# Connections.net
KiCad netlist of a schematic drawn in Altium Designer
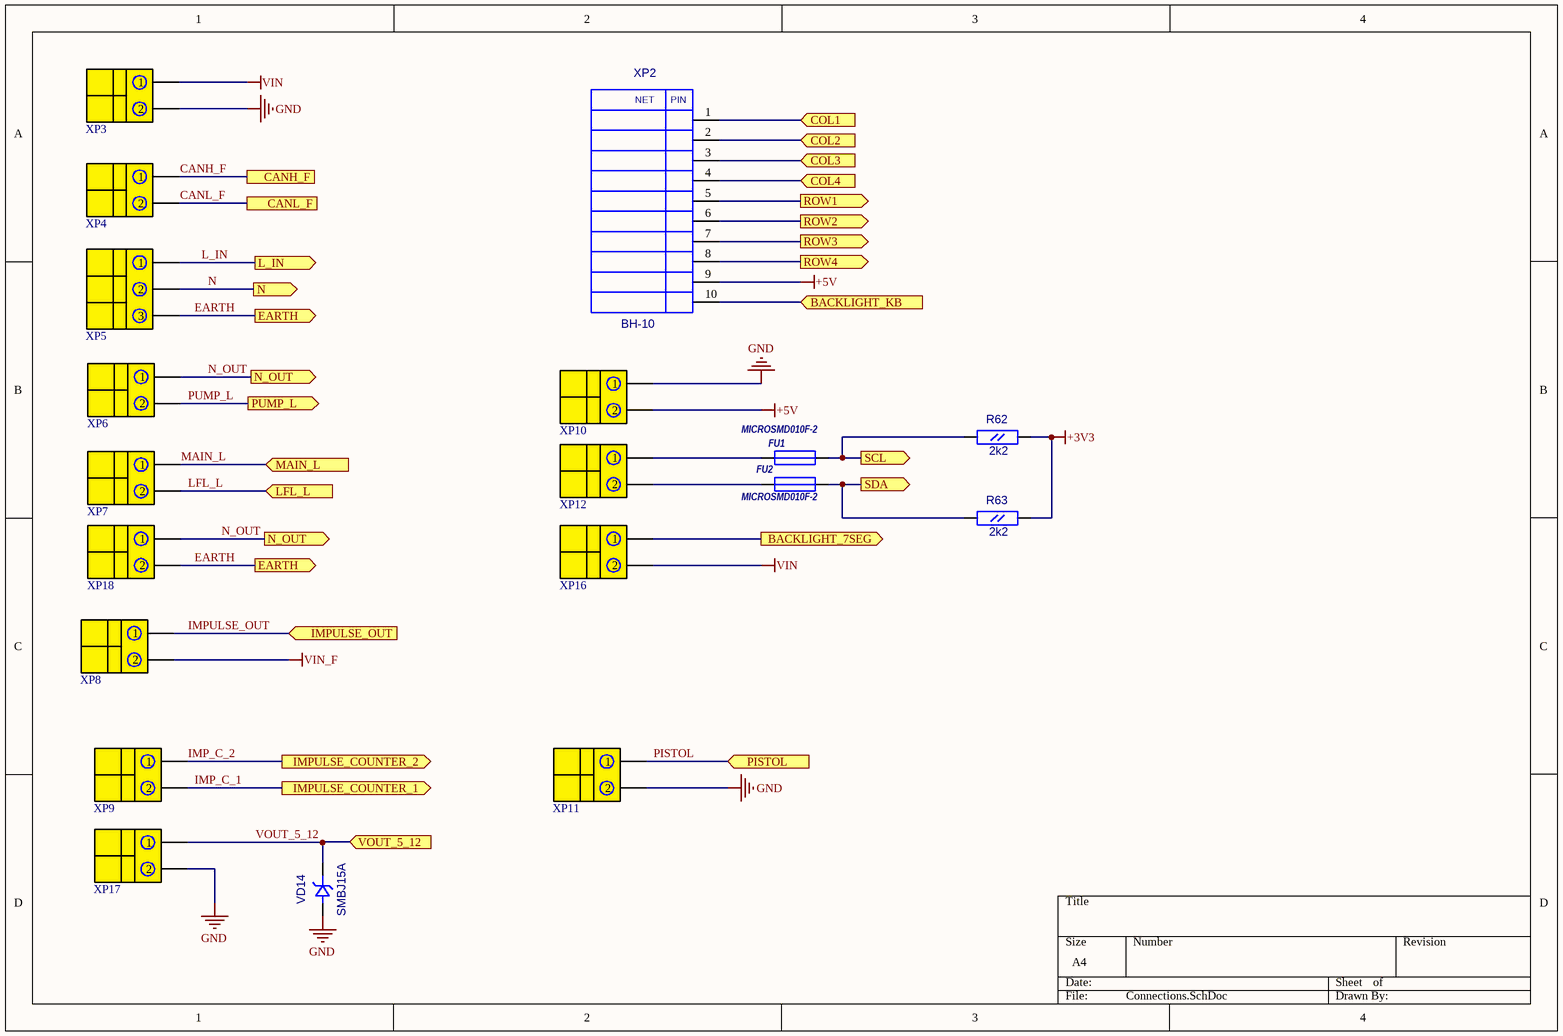
[diagram p0: Connections.SchDoc]

(export (version "E")
  (design (tool "Eeschema 10.0.6"))
  (components
    (comp (ref "FU1")
      (value "MICROSMD010F-2")
      (footprint "RC1210")
      (description "MICROSMD")
      (libsource (lib "gprs_modem_2") (part "MICROSMD"))
    )
    (comp (ref "FU2")
      (value "MICROSMD010F-2")
      (footprint "RC1210")
      (description "MICROSMD")
      (libsource (lib "gprs_modem_2") (part "MICROSMD"))
    )
    (comp (ref "R62")
      (value "2k2")
      (footprint "RC0603")
      (description "RC0603")
      (libsource (lib "gprs_modem_2") (part "RC0603"))
    )
    (comp (ref "R63")
      (value "2k2")
      (footprint "RC0603")
      (description "RC0603")
      (libsource (lib "gprs_modem_2") (part "RC0603"))
    )
    (comp (ref "VD14")
      (value "SMBJ15A")
      (footprint "SMB")
      (description "SMBJ")
      (libsource (lib "gprs_modem_2") (part "SMBJ"))
    )
    (comp (ref "XP2") (value "BH-10") (footprint "BH-10") (libsource (lib "gprs_modem_2") (part "BH-10")))
    (comp (ref "XP3")
      (value "DG330-2PIN")
      (footprint "DG330-2PIN")
      (libsource (lib "gprs_modem_2") (part "DG330-2PIN"))
    )
    (comp (ref "XP4")
      (value "DG330-2PIN")
      (footprint "DG330-2PIN")
      (libsource (lib "gprs_modem_2") (part "DG330-2PIN"))
    )
    (comp (ref "XP5")
      (value "DG330-3PIN")
      (footprint "DG330-3PIN")
      (libsource (lib "gprs_modem_2") (part "DG330-3PIN"))
    )
    (comp (ref "XP6")
      (value "DG330-2PIN")
      (footprint "DG330-2PIN")
      (libsource (lib "gprs_modem_2") (part "DG330-2PIN"))
    )
    (comp (ref "XP7")
      (value "DG330-2PIN")
      (footprint "DG330-2PIN")
      (libsource (lib "gprs_modem_2") (part "DG330-2PIN"))
    )
    (comp (ref "XP8")
      (value "DG330-2PIN")
      (footprint "DG330-2PIN")
      (libsource (lib "gprs_modem_2") (part "DG330-2PIN"))
    )
    (comp (ref "XP9")
      (value "DG330-2PIN")
      (footprint "DG330-2PIN")
      (libsource (lib "gprs_modem_2") (part "DG330-2PIN"))
    )
    (comp (ref "XP10")
      (value "DG330-2PIN")
      (footprint "DG330-2PIN")
      (libsource (lib "gprs_modem_2") (part "DG330-2PIN"))
    )
    (comp (ref "XP11")
      (value "DG330-2PIN")
      (footprint "DG330-2PIN")
      (libsource (lib "gprs_modem_2") (part "DG330-2PIN"))
    )
    (comp (ref "XP12")
      (value "DG330-2PIN")
      (footprint "DG330-2PIN")
      (libsource (lib "gprs_modem_2") (part "DG330-2PIN"))
    )
    (comp (ref "XP16")
      (value "DG330-2PIN")
      (footprint "DG330-2PIN")
      (libsource (lib "gprs_modem_2") (part "DG330-2PIN"))
    )
    (comp (ref "XP17")
      (value "DG330-2PIN")
      (footprint "DG330-2PIN")
      (libsource (lib "gprs_modem_2") (part "DG330-2PIN"))
    )
    (comp (ref "XP18")
      (value "DG330-2PIN")
      (footprint "DG330-2PIN")
      (libsource (lib "gprs_modem_2") (part "DG330-2PIN"))
    )
  )
  (nets
    (net (code "1") (name "+3V3") (class "Default")
      (node (ref "R62") (pin "2") (pinfunction "B_2") (pintype "passive"))
      (node (ref "R63") (pin "2") (pinfunction "B_2") (pintype "passive"))
    )
    (net (code "2") (name "+5V") (class "Default")
      (node (ref "XP10") (pin "2") (pinfunction "2_2") (pintype "passive"))
      (node (ref "XP2") (pin "9") (pinfunction "9_9") (pintype "passive"))
    )
    (net (code "3") (name "/BACKLIGHT_7SEG") (class "Default")
      (node (ref "XP16") (pin "1") (pinfunction "1_1") (pintype "passive"))
    )
    (net (code "4") (name "/BACKLIGHT_KB") (class "Default")
      (node (ref "XP2") (pin "10") (pinfunction "10_10") (pintype "passive"))
    )
    (net (code "5") (name "/CANH_F") (class "Default")
      (node (ref "XP4") (pin "1") (pinfunction "1_1") (pintype "passive"))
    )
    (net (code "6") (name "/CANL_F") (class "Default")
      (node (ref "XP4") (pin "2") (pinfunction "2_2") (pintype "passive"))
    )
    (net (code "7") (name "/COL1") (class "Default")
      (node (ref "XP2") (pin "1") (pinfunction "1_1") (pintype "passive"))
    )
    (net (code "8") (name "/COL2") (class "Default")
      (node (ref "XP2") (pin "2") (pinfunction "2_2") (pintype "passive"))
    )
    (net (code "9") (name "/COL3") (class "Default")
      (node (ref "XP2") (pin "3") (pinfunction "3_3") (pintype "passive"))
    )
    (net (code "10") (name "/COL4") (class "Default")
      (node (ref "XP2") (pin "4") (pinfunction "4_4") (pintype "passive"))
    )
    (net (code "11") (name "/EARTH") (class "Default")
      (node (ref "XP18") (pin "2") (pinfunction "2_2") (pintype "passive"))
      (node (ref "XP5") (pin "3") (pinfunction "3_3") (pintype "passive"))
    )
    (net (code "12") (name "/IMPULSE_OUT") (class "Default")
      (node (ref "XP8") (pin "1") (pinfunction "1_1") (pintype "passive"))
    )
    (net (code "13") (name "/IMP_C_1") (class "Default")
      (node (ref "XP9") (pin "2") (pinfunction "2_2") (pintype "passive"))
    )
    (net (code "14") (name "/IMP_C_2") (class "Default")
      (node (ref "XP9") (pin "1") (pinfunction "1_1") (pintype "passive"))
    )
    (net (code "15") (name "/LFL_L") (class "Default")
      (node (ref "XP7") (pin "2") (pinfunction "2_2") (pintype "passive"))
    )
    (net (code "16") (name "/L_IN") (class "Default")
      (node (ref "XP5") (pin "1") (pinfunction "1_1") (pintype "passive"))
    )
    (net (code "17") (name "/MAIN_L") (class "Default")
      (node (ref "XP7") (pin "1") (pinfunction "1_1") (pintype "passive"))
    )
    (net (code "18") (name "/N") (class "Default")
      (node (ref "XP5") (pin "2") (pinfunction "2_2") (pintype "passive"))
    )
    (net (code "19") (name "/N_OUT") (class "Default")
      (node (ref "XP18") (pin "1") (pinfunction "1_1") (pintype "passive"))
      (node (ref "XP6") (pin "1") (pinfunction "1_1") (pintype "passive"))
    )
    (net (code "20") (name "/PISTOL") (class "Default")
      (node (ref "XP11") (pin "1") (pinfunction "1_1") (pintype "passive"))
    )
    (net (code "21") (name "/PUMP_L") (class "Default")
      (node (ref "XP6") (pin "2") (pinfunction "2_2") (pintype "passive"))
    )
    (net (code "22") (name "/ROW1") (class "Default")
      (node (ref "XP2") (pin "5") (pinfunction "5_5") (pintype "passive"))
    )
    (net (code "23") (name "/ROW2") (class "Default")
      (node (ref "XP2") (pin "6") (pinfunction "6_6") (pintype "passive"))
    )
    (net (code "24") (name "/ROW3") (class "Default")
      (node (ref "XP2") (pin "7") (pinfunction "7_7") (pintype "passive"))
    )
    (net (code "25") (name "/ROW4") (class "Default")
      (node (ref "XP2") (pin "8") (pinfunction "8_8") (pintype "passive"))
    )
    (net (code "26") (name "/SCL") (class "Default")
      (node (ref "FU1") (pin "2") (pintype "passive"))
      (node (ref "R62") (pin "1") (pinfunction "A_1") (pintype "passive"))
    )
    (net (code "27") (name "/SDA") (class "Default")
      (node (ref "FU2") (pin "2") (pintype "passive"))
      (node (ref "R63") (pin "1") (pinfunction "A_1") (pintype "passive"))
    )
    (net (code "28") (name "/VOUT_5_12") (class "Default")
      (node (ref "VD14") (pin "2") (pinfunction "K_2") (pintype "passive"))
      (node (ref "XP17") (pin "1") (pinfunction "1_1") (pintype "passive"))
    )
    (net (code "29") (name "GND") (class "Default")
      (node (ref "VD14") (pin "1") (pinfunction "A_1") (pintype "passive"))
      (node (ref "XP10") (pin "1") (pinfunction "1_1") (pintype "passive"))
      (node (ref "XP11") (pin "2") (pinfunction "2_2") (pintype "passive"))
      (node (ref "XP17") (pin "2") (pinfunction "2_2") (pintype "passive"))
      (node (ref "XP3") (pin "2") (pinfunction "2_2") (pintype "passive"))
    )
    (net (code "30") (name "Net-(FU1-Pad1)") (class "Default")
      (node (ref "FU1") (pin "1") (pintype "passive"))
      (node (ref "XP12") (pin "1") (pinfunction "1_1") (pintype "passive"))
    )
    (net (code "31") (name "Net-(FU2-Pad1)") (class "Default")
      (node (ref "FU2") (pin "1") (pintype "passive"))
      (node (ref "XP12") (pin "2") (pinfunction "2_2") (pintype "passive"))
    )
    (net (code "32") (name "VIN") (class "Default")
      (node (ref "XP16") (pin "2") (pinfunction "2_2") (pintype "passive"))
      (node (ref "XP3") (pin "1") (pinfunction "1_1") (pintype "passive"))
    )
    (net (code "33") (name "VIN_F") (class "Default")
      (node (ref "XP8") (pin "2") (pinfunction "2_2") (pintype "passive"))
    )
  )
)
